# ProtoPi-v1.net
KiCad netlist of a schematic drawn in EAGLE
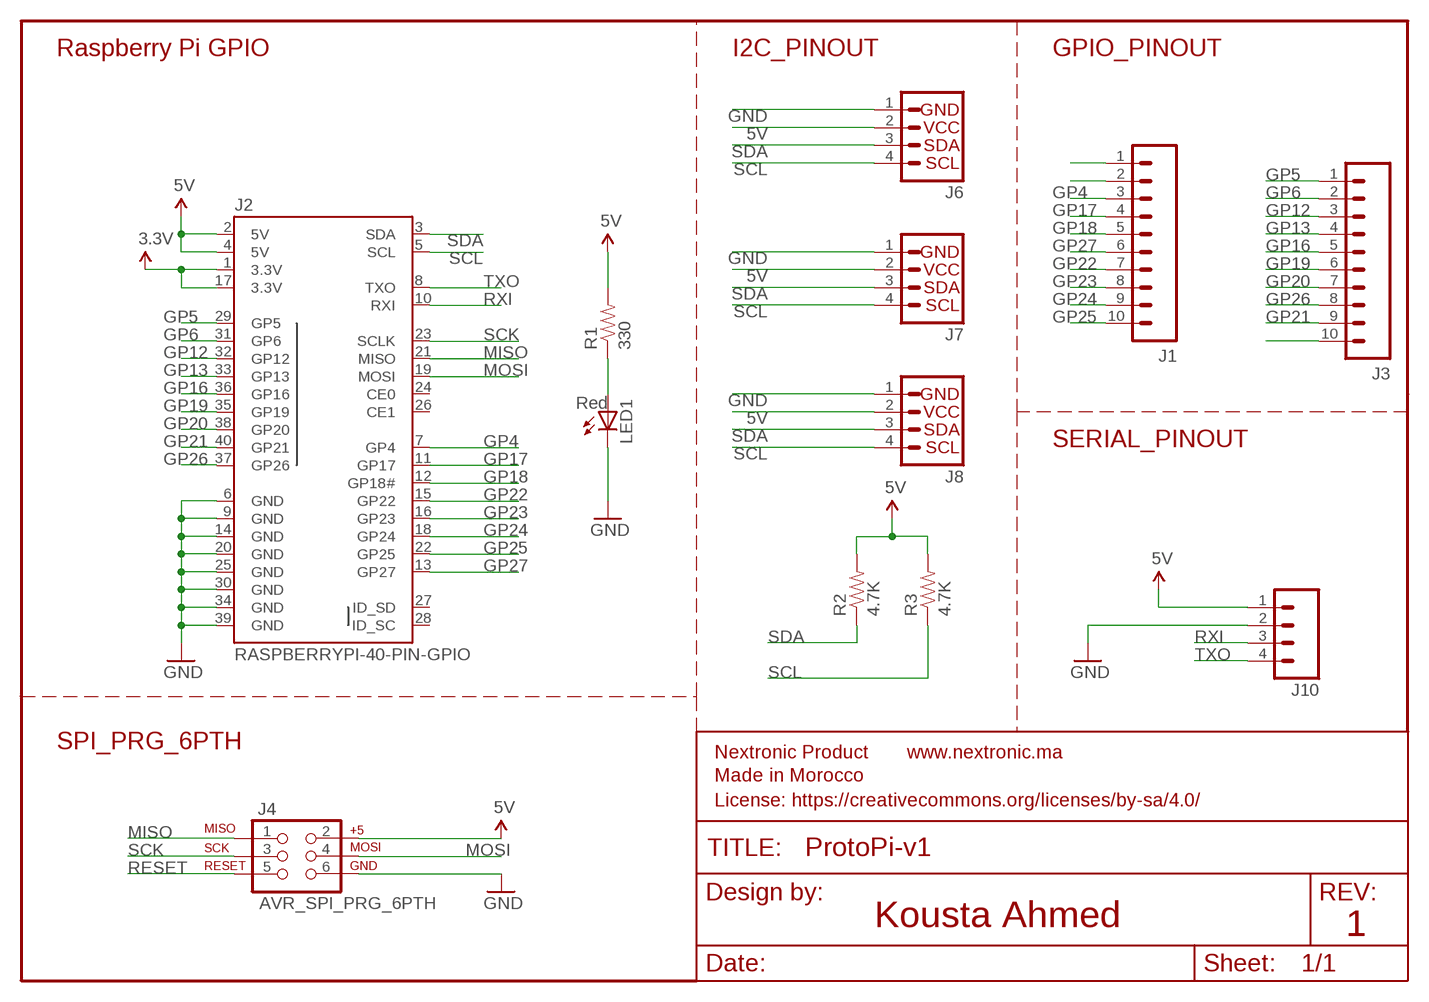
[diagram p0: schematic, sheet 1]

(export (version "E")
  (design (tool "Eeschema 10.0.6"))
  (components
    (comp (ref "FRAME1")
      (value "FRAME-LETTER")
      (footprint "eagle-import:CREATIVE_COMMONS")
      (libsource (lib "eagle-import") (part "FRAME-LETTER"))
    )
    (comp (ref "J1")
      (value "M10SILK_FEMALE_PTH")
      (footprint "eagle-import:1X10")
      (libsource (lib "eagle-import") (part "M10SILK_FEMALE_PTH"))
    )
    (comp (ref "J2")
      (value "RASPBERRYPI-40-PIN-GPIO")
      (footprint "eagle-import:2X20-SHROUDED")
      (libsource (lib "eagle-import") (part "RASPBERRYPI-40-PIN-GPIO"))
    )
    (comp (ref "J3")
      (value "M10SILK_FEMALE_PTH")
      (footprint "eagle-import:1X10")
      (libsource (lib "eagle-import") (part "M10SILK_FEMALE_PTH"))
    )
    (comp (ref "J4")
      (value "AVR_SPI_PRG_6PTH")
      (footprint "eagle-import:2X3")
      (libsource (lib "eagle-import") (part "AVR_SPI_PRG_6PTH"))
    )
    (comp (ref "J6")
      (value "I2C_STANDARD")
      (footprint "eagle-import:1X04")
      (libsource (lib "eagle-import") (part "I2C_STANDARD"))
    )
    (comp (ref "J7")
      (value "I2C_STANDARD")
      (footprint "eagle-import:1X04")
      (libsource (lib "eagle-import") (part "I2C_STANDARD"))
    )
    (comp (ref "J8")
      (value "I2C_STANDARD")
      (footprint "eagle-import:1X04")
      (libsource (lib "eagle-import") (part "I2C_STANDARD"))
    )
    (comp (ref "J10")
      (value "M04PTH")
      (footprint "eagle-import:1X04")
      (libsource (lib "eagle-import") (part "M04PTH"))
    )
    (comp (ref "LED1")
      (value "Red")
      (footprint "eagle-import:LED5MM")
      (libsource (lib "eagle-import") (part "LED5MM"))
    )
    (comp (ref "R1")
      (value "330")
      (footprint "eagle-import:AXIAL-0.3")
      (libsource (lib "eagle-import") (part "RESISTORPTH1"))
    )
    (comp (ref "R2")
      (value "4.7K")
      (footprint "eagle-import:AXIAL-0.3")
      (libsource (lib "eagle-import") (part "RESISTORPTH1"))
    )
    (comp (ref "R3")
      (value "4.7K")
      (footprint "eagle-import:AXIAL-0.3")
      (libsource (lib "eagle-import") (part "RESISTORPTH1"))
    )
  )
  (nets
    (net (code "1") (name "/GP4") (class "Default")
      (node (ref "J1") (pin "3") (pinfunction "3_3") (pintype "passive"))
      (node (ref "J2") (pin "7") (pinfunction "GP4_7") (pintype "bidirectional"))
    )
    (net (code "2") (name "/GP5") (class "Default")
      (node (ref "J2") (pin "29") (pinfunction "GP5_29") (pintype "bidirectional"))
      (node (ref "J3") (pin "1") (pinfunction "1_1") (pintype "passive"))
    )
    (net (code "3") (name "/GP6") (class "Default")
      (node (ref "J2") (pin "31") (pinfunction "GP6_31") (pintype "bidirectional"))
      (node (ref "J3") (pin "2") (pinfunction "2_2") (pintype "passive"))
    )
    (net (code "4") (name "/GP12") (class "Default")
      (node (ref "J2") (pin "32") (pinfunction "GP12_32") (pintype "bidirectional"))
      (node (ref "J3") (pin "3") (pinfunction "3_3") (pintype "passive"))
    )
    (net (code "5") (name "/GP13") (class "Default")
      (node (ref "J2") (pin "33") (pinfunction "GP13_33") (pintype "bidirectional"))
      (node (ref "J3") (pin "4") (pinfunction "4_4") (pintype "passive"))
    )
    (net (code "6") (name "/GP16") (class "Default")
      (node (ref "J2") (pin "36") (pinfunction "GP16_36") (pintype "bidirectional"))
      (node (ref "J3") (pin "5") (pinfunction "5_5") (pintype "passive"))
    )
    (net (code "7") (name "/GP17") (class "Default")
      (node (ref "J1") (pin "4") (pinfunction "4_4") (pintype "passive"))
      (node (ref "J2") (pin "11") (pinfunction "GP17_11") (pintype "bidirectional"))
    )
    (net (code "8") (name "/GP18") (class "Default")
      (node (ref "J1") (pin "5") (pinfunction "5_5") (pintype "passive"))
      (node (ref "J2") (pin "12") (pinfunction "GP18#_12") (pintype "bidirectional"))
    )
    (net (code "9") (name "/GP19") (class "Default")
      (node (ref "J2") (pin "35") (pinfunction "GP19_35") (pintype "bidirectional"))
      (node (ref "J3") (pin "6") (pinfunction "6_6") (pintype "passive"))
    )
    (net (code "10") (name "/GP20") (class "Default")
      (node (ref "J2") (pin "38") (pinfunction "GP20_38") (pintype "bidirectional"))
      (node (ref "J3") (pin "7") (pinfunction "7_7") (pintype "passive"))
    )
    (net (code "11") (name "/GP21") (class "Default")
      (node (ref "J2") (pin "40") (pinfunction "GP21_40") (pintype "bidirectional"))
      (node (ref "J3") (pin "9") (pinfunction "9_9") (pintype "passive"))
    )
    (net (code "12") (name "/GP22") (class "Default")
      (node (ref "J1") (pin "7") (pinfunction "7_7") (pintype "passive"))
      (node (ref "J2") (pin "15") (pinfunction "GP22_15") (pintype "bidirectional"))
    )
    (net (code "13") (name "/GP23") (class "Default")
      (node (ref "J1") (pin "8") (pinfunction "8_8") (pintype "passive"))
      (node (ref "J2") (pin "16") (pinfunction "GP23_16") (pintype "bidirectional"))
    )
    (net (code "14") (name "/GP24") (class "Default")
      (node (ref "J1") (pin "9") (pinfunction "9_9") (pintype "passive"))
      (node (ref "J2") (pin "18") (pinfunction "GP24_18") (pintype "bidirectional"))
    )
    (net (code "15") (name "/GP25") (class "Default")
      (node (ref "J1") (pin "10") (pinfunction "10_10") (pintype "passive"))
      (node (ref "J2") (pin "22") (pinfunction "GP25_22") (pintype "bidirectional"))
    )
    (net (code "16") (name "/GP26") (class "Default")
      (node (ref "J2") (pin "37") (pinfunction "GP26_37") (pintype "bidirectional"))
      (node (ref "J3") (pin "8") (pinfunction "8_8") (pintype "passive"))
    )
    (net (code "17") (name "/GP27") (class "Default")
      (node (ref "J1") (pin "6") (pinfunction "6_6") (pintype "passive"))
      (node (ref "J2") (pin "13") (pinfunction "GP27_13") (pintype "bidirectional"))
    )
    (net (code "18") (name "/MISO") (class "Default")
      (node (ref "J2") (pin "21") (pinfunction "MISO_21") (pintype "input"))
      (node (ref "J4") (pin "1") (pinfunction "1_1") (pintype "passive"))
    )
    (net (code "19") (name "/MOSI") (class "Default")
      (node (ref "J2") (pin "19") (pinfunction "MOSI_19") (pintype "output"))
      (node (ref "J4") (pin "4") (pinfunction "4_4") (pintype "passive"))
    )
    (net (code "20") (name "/RESET") (class "Default")
      (node (ref "J4") (pin "5") (pinfunction "5_5") (pintype "passive"))
    )
    (net (code "21") (name "/RXI") (class "Default")
      (node (ref "J10") (pin "3") (pinfunction "3_3") (pintype "passive"))
      (node (ref "J2") (pin "10") (pinfunction "RXI_10") (pintype "input"))
    )
    (net (code "22") (name "/SCK") (class "Default")
      (node (ref "J2") (pin "23") (pinfunction "SCLK_23") (pintype "output"))
      (node (ref "J4") (pin "3") (pinfunction "3_3") (pintype "passive"))
    )
    (net (code "23") (name "/SCL") (class "Default")
      (node (ref "J2") (pin "5") (pinfunction "SCL_5") (pintype "bidirectional"))
      (node (ref "J6") (pin "4") (pinfunction "4_4") (pintype "passive"))
      (node (ref "J7") (pin "4") (pinfunction "4_4") (pintype "passive"))
      (node (ref "J8") (pin "4") (pinfunction "4_4") (pintype "passive"))
      (node (ref "R3") (pin "P$1") (pinfunction "1_P$1") (pintype "passive"))
    )
    (net (code "24") (name "/SDA") (class "Default")
      (node (ref "J2") (pin "3") (pinfunction "SDA_3") (pintype "bidirectional"))
      (node (ref "J6") (pin "3") (pinfunction "3_3") (pintype "passive"))
      (node (ref "J7") (pin "3") (pinfunction "3_3") (pintype "passive"))
      (node (ref "J8") (pin "3") (pinfunction "3_3") (pintype "passive"))
      (node (ref "R2") (pin "P$1") (pinfunction "1_P$1") (pintype "passive"))
    )
    (net (code "25") (name "/TXO") (class "Default")
      (node (ref "J10") (pin "4") (pinfunction "4_4") (pintype "passive"))
      (node (ref "J2") (pin "8") (pinfunction "TXO_8") (pintype "output"))
    )
    (net (code "26") (name "3.3V") (class "Default")
      (node (ref "J2") (pin "1") (pinfunction "3.3V_1") (pintype "power_in"))
      (node (ref "J2") (pin "17") (pinfunction "3.3V_17") (pintype "power_in"))
    )
    (net (code "27") (name "5V") (class "Default")
      (node (ref "J10") (pin "1") (pinfunction "1_1") (pintype "passive"))
      (node (ref "J2") (pin "2") (pinfunction "5V_2") (pintype "power_in"))
      (node (ref "J2") (pin "4") (pinfunction "5V_4") (pintype "power_in"))
      (node (ref "J4") (pin "2") (pinfunction "2_2") (pintype "passive"))
      (node (ref "J6") (pin "2") (pinfunction "2_2") (pintype "passive"))
      (node (ref "J7") (pin "2") (pinfunction "2_2") (pintype "passive"))
      (node (ref "J8") (pin "2") (pinfunction "2_2") (pintype "passive"))
      (node (ref "R1") (pin "P$2") (pinfunction "2_P$2") (pintype "passive"))
      (node (ref "R2") (pin "P$2") (pinfunction "2_P$2") (pintype "passive"))
      (node (ref "R3") (pin "P$2") (pinfunction "2_P$2") (pintype "passive"))
    )
    (net (code "28") (name "GND") (class "Default")
      (node (ref "J10") (pin "2") (pinfunction "2_2") (pintype "passive"))
      (node (ref "J2") (pin "14") (pinfunction "GND_14") (pintype "power_in"))
      (node (ref "J2") (pin "20") (pinfunction "GND_20") (pintype "power_in"))
      (node (ref "J2") (pin "25") (pinfunction "GND_25") (pintype "power_in"))
      (node (ref "J2") (pin "30") (pinfunction "GND_30") (pintype "power_in"))
      (node (ref "J2") (pin "34") (pinfunction "GND_34") (pintype "power_in"))
      (node (ref "J2") (pin "39") (pinfunction "GND_39") (pintype "power_in"))
      (node (ref "J2") (pin "6") (pinfunction "GND_6") (pintype "power_in"))
      (node (ref "J2") (pin "9") (pinfunction "GND_9") (pintype "power_in"))
      (node (ref "J4") (pin "6") (pinfunction "6_6") (pintype "passive"))
      (node (ref "J6") (pin "1") (pinfunction "1_1") (pintype "passive"))
      (node (ref "J7") (pin "1") (pinfunction "1_1") (pintype "passive"))
      (node (ref "J8") (pin "1") (pinfunction "1_1") (pintype "passive"))
      (node (ref "LED1") (pin "K") (pinfunction "C_K") (pintype "passive"))
    )
    (net (code "29") (name "Net-(R1-1)") (class "Default")
      (node (ref "LED1") (pin "A") (pinfunction "A_A") (pintype "passive"))
      (node (ref "R1") (pin "P$1") (pinfunction "1_P$1") (pintype "passive"))
    )
    (net (code "30") (name "unconnected-(J1-Pad1)") (class "Default")
      (node (ref "J1") (pin "1") (pinfunction "1_1") (pintype "passive"))
    )
    (net (code "31") (name "unconnected-(J1-Pad2)") (class "Default")
      (node (ref "J1") (pin "2") (pinfunction "2_2") (pintype "passive"))
    )
    (net (code "32") (name "unconnected-(J2-CE0-Pad24)") (class "Default")
      (node (ref "J2") (pin "24") (pinfunction "CE0_24") (pintype "output"))
    )
    (net (code "33") (name "unconnected-(J2-CE1-Pad26)") (class "Default")
      (node (ref "J2") (pin "26") (pinfunction "CE1_26") (pintype "output"))
    )
    (net (code "34") (name "unconnected-(J2-ID_SC-Pad28)") (class "Default")
      (node (ref "J2") (pin "28") (pinfunction "ID_SC_28") (pintype "bidirectional"))
    )
    (net (code "35") (name "unconnected-(J2-ID_SD-Pad27)") (class "Default")
      (node (ref "J2") (pin "27") (pinfunction "ID_SD_27") (pintype "bidirectional"))
    )
    (net (code "36") (name "unconnected-(J3-Pad10)") (class "Default")
      (node (ref "J3") (pin "10") (pinfunction "10_10") (pintype "passive"))
    )
  )
)
